# MRCS-Dual-3-Position-Semaphore-Controlle.net
KiCad netlist of a schematic drawn in EAGLE
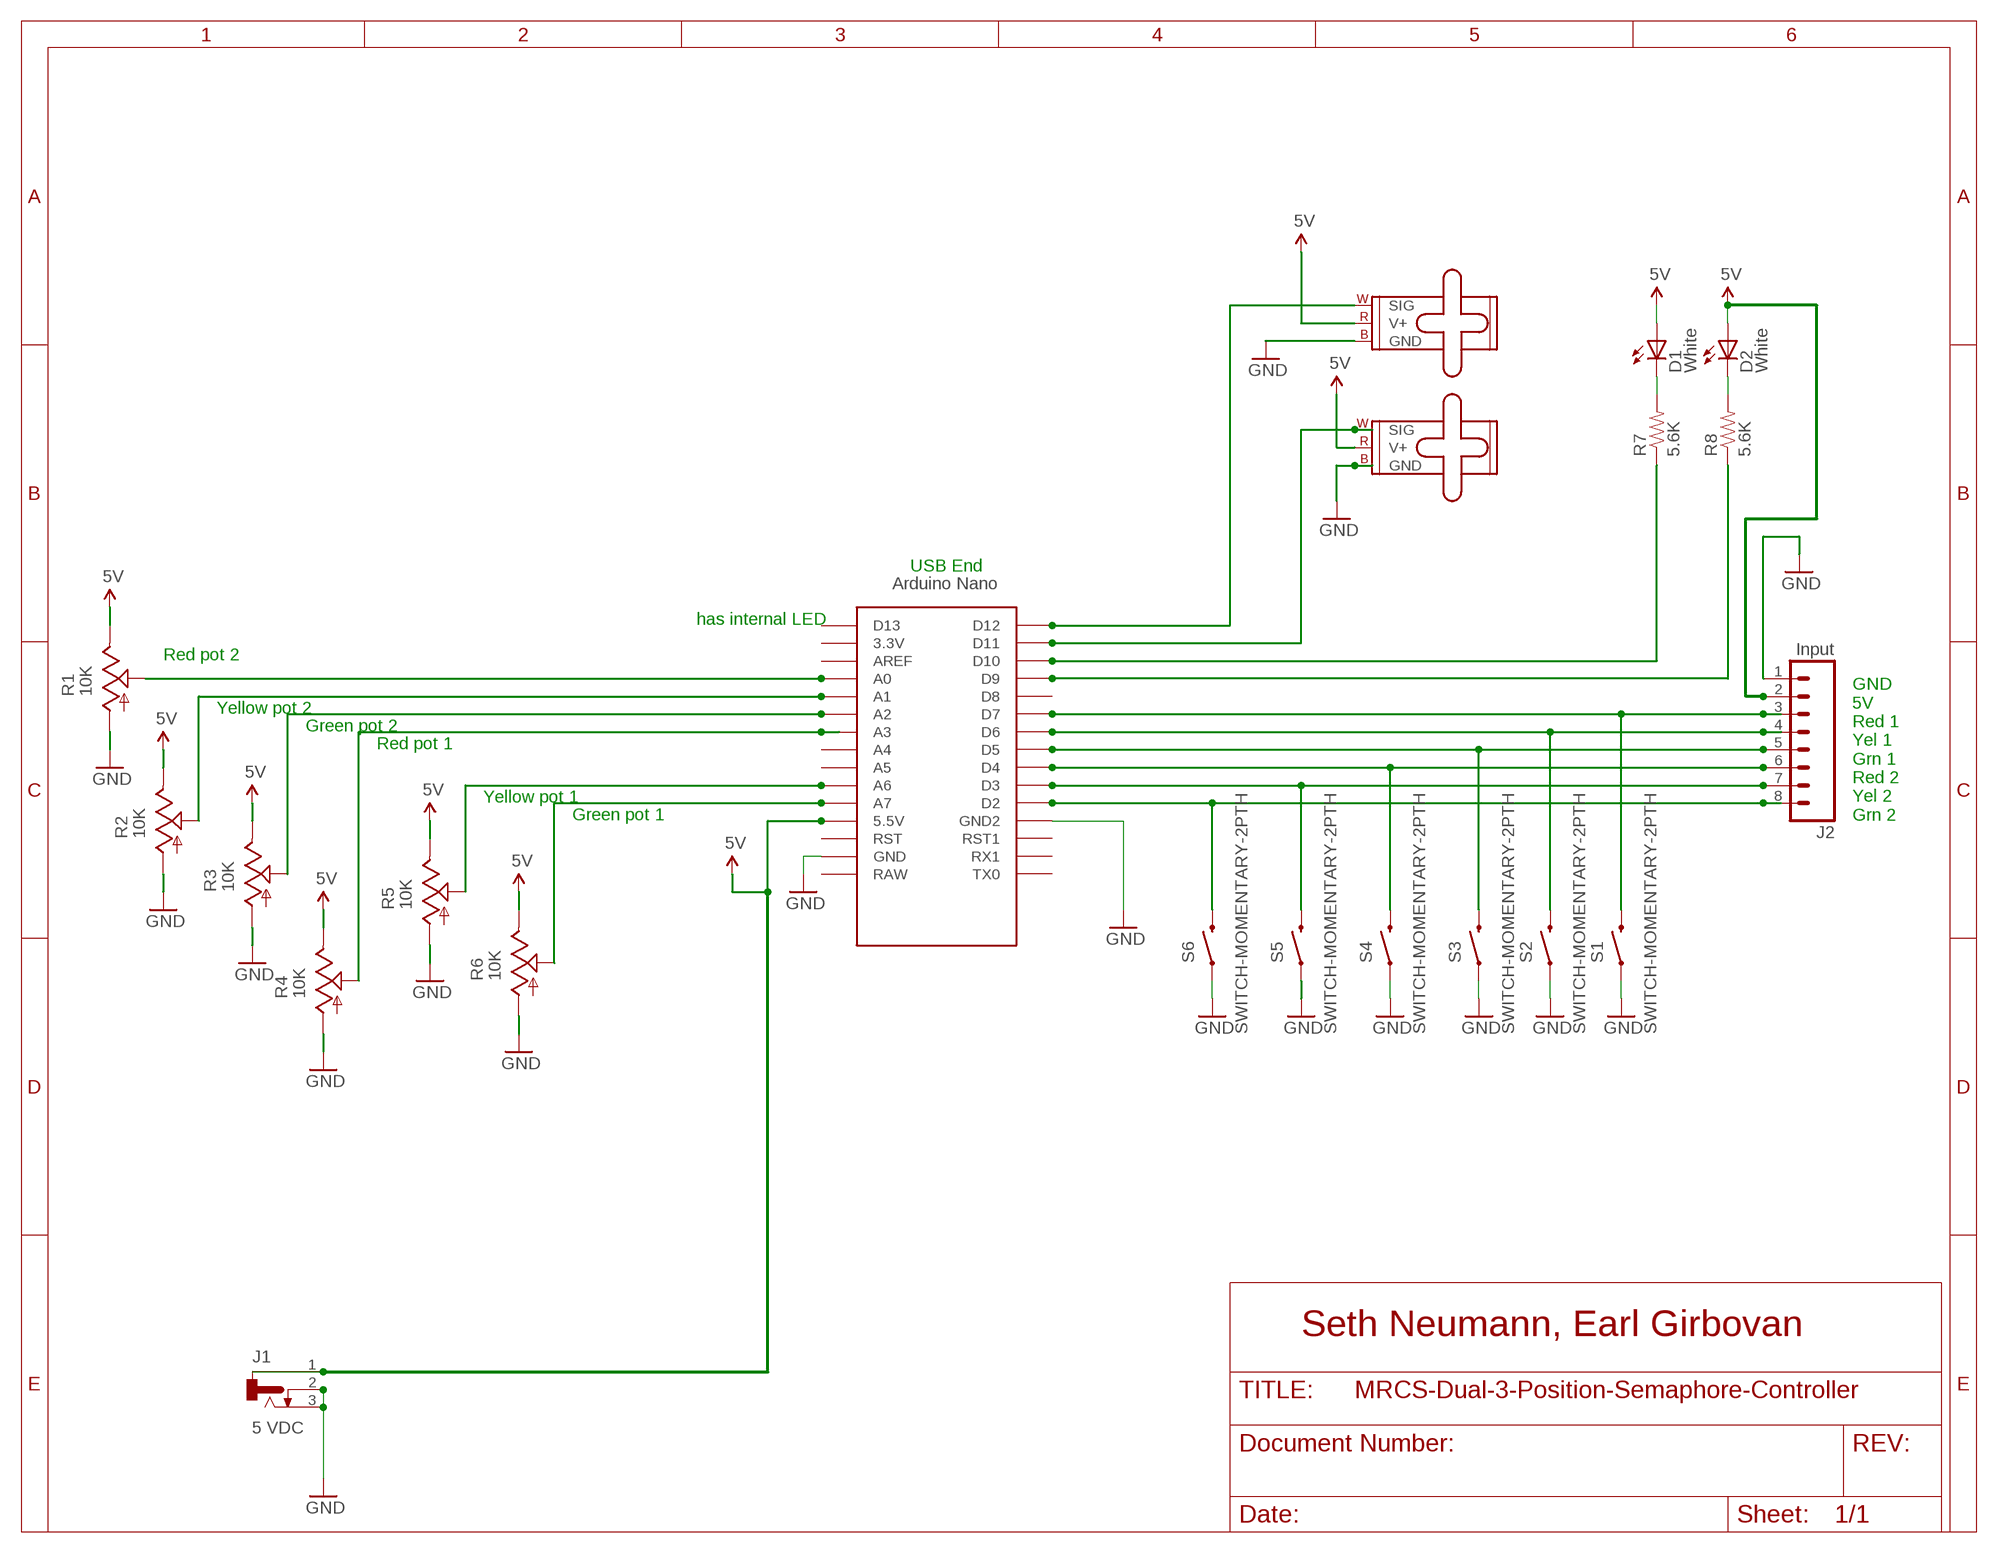
[diagram p0: schematic, sheet 1]

(export (version "E")
  (design (tool "Eeschema 10.0.6"))
  (components
    (comp (ref "D1")
      (value "White")
      (footprint "eagle-import:LED3MM")
      (libsource (lib "eagle-import") (part "LEDLED3MM"))
    )
    (comp (ref "D2")
      (value "White")
      (footprint "eagle-import:LED3MM")
      (libsource (lib "eagle-import") (part "LEDLED3MM"))
    )
    (comp (ref "J1")
      (value "5 VDC")
      (footprint "eagle-import:DCJ0202")
      (libsource (lib "eagle-import") (part "CONNECTOR-DC-POWER-RA"))
    )
    (comp (ref "J2")
      (value "Input")
      (footprint "eagle-import:1X08_LOCK")
      (libsource (lib "eagle-import") (part "CONNECTOR-M08LOCK"))
    )
    (comp (ref "M1")
      (value "SMALL_SERVO")
      (footprint "eagle-import:1X03")
      (libsource (lib "eagle-import") (part "SMALL_SERVO"))
    )
    (comp (ref "M2")
      (value "SMALL_SERVO")
      (footprint "eagle-import:1X03")
      (libsource (lib "eagle-import") (part "SMALL_SERVO"))
    )
    (comp (ref "NANO")
      (value "NANO")
      (footprint "eagle-import:NANO")
      (libsource (lib "eagle-import") (part "NANO"))
    )
    (comp (ref "R1")
      (value "10K")
      (footprint "eagle-import:RS3")
      (libsource (lib "eagle-import") (part "TRIM_US-RS3"))
    )
    (comp (ref "R2")
      (value "10K")
      (footprint "eagle-import:RS3")
      (libsource (lib "eagle-import") (part "TRIM_US-RS3"))
    )
    (comp (ref "R3")
      (value "10K")
      (footprint "eagle-import:RS3")
      (libsource (lib "eagle-import") (part "TRIM_US-RS3"))
    )
    (comp (ref "R4")
      (value "10K")
      (footprint "eagle-import:RS3")
      (libsource (lib "eagle-import") (part "TRIM_US-RS3"))
    )
    (comp (ref "R5")
      (value "10K")
      (footprint "eagle-import:RS3")
      (libsource (lib "eagle-import") (part "TRIM_US-RS3"))
    )
    (comp (ref "R6")
      (value "10K")
      (footprint "eagle-import:RS3")
      (libsource (lib "eagle-import") (part "TRIM_US-RS3"))
    )
    (comp (ref "R7")
      (value "5.6K")
      (footprint "eagle-import:AXIAL-0.4")
      (libsource (lib "eagle-import") (part "RESISTORPTH-1/4W"))
    )
    (comp (ref "R8")
      (value "5.6K")
      (footprint "eagle-import:AXIAL-0.4")
      (libsource (lib "eagle-import") (part "RESISTORPTH-1/4W"))
    )
    (comp (ref "S1")
      (value "SWITCH-MOMENTARY-2PTH")
      (footprint "eagle-import:TACTILE-PTH")
      (libsource (lib "eagle-import") (part "SWITCH-MOMENTARY-2PTH"))
    )
    (comp (ref "S2")
      (value "SWITCH-MOMENTARY-2PTH")
      (footprint "eagle-import:TACTILE-PTH")
      (libsource (lib "eagle-import") (part "SWITCH-MOMENTARY-2PTH"))
    )
    (comp (ref "S3")
      (value "SWITCH-MOMENTARY-2PTH")
      (footprint "eagle-import:TACTILE-PTH")
      (libsource (lib "eagle-import") (part "SWITCH-MOMENTARY-2PTH"))
    )
    (comp (ref "S4")
      (value "SWITCH-MOMENTARY-2PTH")
      (footprint "eagle-import:TACTILE-PTH")
      (libsource (lib "eagle-import") (part "SWITCH-MOMENTARY-2PTH"))
    )
    (comp (ref "S5")
      (value "SWITCH-MOMENTARY-2PTH")
      (footprint "eagle-import:TACTILE-PTH")
      (libsource (lib "eagle-import") (part "SWITCH-MOMENTARY-2PTH"))
    )
    (comp (ref "S6")
      (value "SWITCH-MOMENTARY-2PTH")
      (footprint "eagle-import:TACTILE-PTH")
      (libsource (lib "eagle-import") (part "SWITCH-MOMENTARY-2PTH"))
    )
  )
  (nets
    (net (code "1") (name "5V") (class "Default")
      (node (ref "D1") (pin "A") (pinfunction "A_A") (pintype "passive"))
      (node (ref "D2") (pin "A") (pinfunction "A_A") (pintype "passive"))
      (node (ref "J1") (pin "1") (pinfunction "1_1") (pintype "passive"))
      (node (ref "J2") (pin "2") (pinfunction "2_2") (pintype "passive"))
      (node (ref "M1") (pin "2") (pinfunction "V+_2") (pintype "bidirectional"))
      (node (ref "M2") (pin "2") (pinfunction "V+_2") (pintype "bidirectional"))
      (node (ref "NANO") (pin "5V") (pinfunction "5.5V_5V") (pintype "bidirectional"))
      (node (ref "R1") (pin "E") (pinfunction "E_E") (pintype "passive"))
      (node (ref "R2") (pin "E") (pinfunction "E_E") (pintype "passive"))
      (node (ref "R3") (pin "E") (pinfunction "E_E") (pintype "passive"))
      (node (ref "R4") (pin "E") (pinfunction "E_E") (pintype "passive"))
      (node (ref "R5") (pin "E") (pinfunction "E_E") (pintype "passive"))
      (node (ref "R6") (pin "E") (pinfunction "E_E") (pintype "passive"))
    )
    (net (code "2") (name "GND") (class "Default")
      (node (ref "J1") (pin "2") (pinfunction "2_2") (pintype "passive"))
      (node (ref "J1") (pin "3") (pinfunction "3_3") (pintype "passive"))
      (node (ref "J2") (pin "1") (pinfunction "1_1") (pintype "passive"))
      (node (ref "M1") (pin "3") (pinfunction "GND_3") (pintype "bidirectional"))
      (node (ref "M2") (pin "3") (pinfunction "GND_3") (pintype "bidirectional"))
      (node (ref "NANO") (pin "GND") (pinfunction "GND_GND") (pintype "bidirectional"))
      (node (ref "NANO") (pin "GND1") (pinfunction "GND2_GND1") (pintype "bidirectional"))
      (node (ref "R1") (pin "A") (pinfunction "A_A") (pintype "passive"))
      (node (ref "R2") (pin "A") (pinfunction "A_A") (pintype "passive"))
      (node (ref "R3") (pin "A") (pinfunction "A_A") (pintype "passive"))
      (node (ref "R4") (pin "A") (pinfunction "A_A") (pintype "passive"))
      (node (ref "R5") (pin "A") (pinfunction "A_A") (pintype "passive"))
      (node (ref "R6") (pin "A") (pinfunction "A_A") (pintype "passive"))
      (node (ref "S1") (pin "1") (pinfunction "1_1") (pintype "passive"))
      (node (ref "S2") (pin "1") (pinfunction "1_1") (pintype "passive"))
      (node (ref "S3") (pin "1") (pinfunction "1_1") (pintype "passive"))
      (node (ref "S4") (pin "1") (pinfunction "1_1") (pintype "passive"))
      (node (ref "S5") (pin "1") (pinfunction "1_1") (pintype "passive"))
      (node (ref "S6") (pin "1") (pinfunction "1_1") (pintype "passive"))
    )
    (net (code "3") (name "Net-(D1-C)") (class "Default")
      (node (ref "D1") (pin "K") (pinfunction "C_K") (pintype "passive"))
      (node (ref "R7") (pin "P$2") (pinfunction "2_P$2") (pintype "passive"))
    )
    (net (code "4") (name "Net-(D2-C)") (class "Default")
      (node (ref "D2") (pin "K") (pinfunction "C_K") (pintype "passive"))
      (node (ref "R8") (pin "P$2") (pinfunction "2_P$2") (pintype "passive"))
    )
    (net (code "5") (name "Net-(M1-SIG)") (class "Default")
      (node (ref "M1") (pin "1") (pinfunction "SIG_1") (pintype "bidirectional"))
      (node (ref "NANO") (pin "D12") (pinfunction "D12_D12") (pintype "bidirectional"))
    )
    (net (code "6") (name "Net-(M2-SIG)") (class "Default")
      (node (ref "M2") (pin "1") (pinfunction "SIG_1") (pintype "bidirectional"))
      (node (ref "NANO") (pin "D11") (pinfunction "D11_D11") (pintype "bidirectional"))
    )
    (net (code "7") (name "Net-(NANO-PadA0)") (class "Default")
      (node (ref "NANO") (pin "A0") (pinfunction "A0_A0") (pintype "bidirectional"))
      (node (ref "R1") (pin "S") (pinfunction "S_S") (pintype "passive"))
    )
    (net (code "8") (name "Net-(NANO-PadA1)") (class "Default")
      (node (ref "NANO") (pin "A1") (pinfunction "A1_A1") (pintype "bidirectional"))
      (node (ref "R2") (pin "S") (pinfunction "S_S") (pintype "passive"))
    )
    (net (code "9") (name "Net-(NANO-PadA2)") (class "Default")
      (node (ref "NANO") (pin "A2") (pinfunction "A2_A2") (pintype "bidirectional"))
      (node (ref "R3") (pin "S") (pinfunction "S_S") (pintype "passive"))
    )
    (net (code "10") (name "Net-(NANO-PadA3)") (class "Default")
      (node (ref "NANO") (pin "A3") (pinfunction "A3_A3") (pintype "bidirectional"))
      (node (ref "R4") (pin "S") (pinfunction "S_S") (pintype "passive"))
    )
    (net (code "11") (name "Net-(NANO-PadA6)") (class "Default")
      (node (ref "NANO") (pin "A6") (pinfunction "A6_A6") (pintype "bidirectional"))
      (node (ref "R5") (pin "S") (pinfunction "S_S") (pintype "passive"))
    )
    (net (code "12") (name "Net-(NANO-PadA7)") (class "Default")
      (node (ref "NANO") (pin "A7") (pinfunction "A7_A7") (pintype "bidirectional"))
      (node (ref "R6") (pin "S") (pinfunction "S_S") (pintype "passive"))
    )
    (net (code "13") (name "Net-(R7-1)") (class "Default")
      (node (ref "NANO") (pin "D10") (pinfunction "D10_D10") (pintype "bidirectional"))
      (node (ref "R7") (pin "P$1") (pinfunction "1_P$1") (pintype "passive"))
    )
    (net (code "14") (name "Net-(R8-1)") (class "Default")
      (node (ref "NANO") (pin "D9") (pinfunction "D9_D9") (pintype "bidirectional"))
      (node (ref "R8") (pin "P$1") (pinfunction "1_P$1") (pintype "passive"))
    )
    (net (code "15") (name "Net-(S1-2)") (class "Default")
      (node (ref "J2") (pin "3") (pinfunction "3_3") (pintype "passive"))
      (node (ref "NANO") (pin "D7") (pinfunction "D7_D7") (pintype "bidirectional"))
      (node (ref "S1") (pin "3") (pinfunction "2_3") (pintype "passive"))
    )
    (net (code "16") (name "Net-(S2-2)") (class "Default")
      (node (ref "J2") (pin "4") (pinfunction "4_4") (pintype "passive"))
      (node (ref "NANO") (pin "D6") (pinfunction "D6_D6") (pintype "bidirectional"))
      (node (ref "S2") (pin "3") (pinfunction "2_3") (pintype "passive"))
    )
    (net (code "17") (name "Net-(S3-2)") (class "Default")
      (node (ref "J2") (pin "5") (pinfunction "5_5") (pintype "passive"))
      (node (ref "NANO") (pin "D5") (pinfunction "D5_D5") (pintype "bidirectional"))
      (node (ref "S3") (pin "3") (pinfunction "2_3") (pintype "passive"))
    )
    (net (code "18") (name "Net-(S4-2)") (class "Default")
      (node (ref "J2") (pin "6") (pinfunction "6_6") (pintype "passive"))
      (node (ref "NANO") (pin "D4") (pinfunction "D4_D4") (pintype "bidirectional"))
      (node (ref "S4") (pin "3") (pinfunction "2_3") (pintype "passive"))
    )
    (net (code "19") (name "Net-(S5-2)") (class "Default")
      (node (ref "J2") (pin "7") (pinfunction "7_7") (pintype "passive"))
      (node (ref "NANO") (pin "D3") (pinfunction "D3_D3") (pintype "bidirectional"))
      (node (ref "S5") (pin "3") (pinfunction "2_3") (pintype "passive"))
    )
    (net (code "20") (name "Net-(S6-2)") (class "Default")
      (node (ref "J2") (pin "8") (pinfunction "8_8") (pintype "passive"))
      (node (ref "NANO") (pin "D2") (pinfunction "D2_D2") (pintype "bidirectional"))
      (node (ref "S6") (pin "3") (pinfunction "2_3") (pintype "passive"))
    )
    (net (code "21") (name "unconnected-(NANO-Pad3.3V)") (class "Default")
      (node (ref "NANO") (pin "3.3V") (pinfunction "3.3V_3.3V") (pintype "bidirectional"))
    )
    (net (code "22") (name "unconnected-(NANO-PadA4)") (class "Default")
      (node (ref "NANO") (pin "A4") (pinfunction "A4_A4") (pintype "bidirectional"))
    )
    (net (code "23") (name "unconnected-(NANO-PadA5)") (class "Default")
      (node (ref "NANO") (pin "A5") (pinfunction "A5_A5") (pintype "bidirectional"))
    )
    (net (code "24") (name "unconnected-(NANO-PadAREF)") (class "Default")
      (node (ref "NANO") (pin "AREF") (pinfunction "AREF_AREF") (pintype "bidirectional"))
    )
    (net (code "25") (name "unconnected-(NANO-PadD8)") (class "Default")
      (node (ref "NANO") (pin "D8") (pinfunction "D8_D8") (pintype "bidirectional"))
    )
    (net (code "26") (name "unconnected-(NANO-PadD13)") (class "Default")
      (node (ref "NANO") (pin "D13") (pinfunction "D13_D13") (pintype "bidirectional"))
    )
    (net (code "27") (name "unconnected-(NANO-PadRAW)") (class "Default")
      (node (ref "NANO") (pin "RAW") (pinfunction "RAW_RAW") (pintype "bidirectional"))
    )
    (net (code "28") (name "unconnected-(NANO-PadRST)") (class "Default")
      (node (ref "NANO") (pin "RST") (pinfunction "RST_RST") (pintype "bidirectional"))
    )
    (net (code "29") (name "unconnected-(NANO-PadRST1)") (class "Default")
      (node (ref "NANO") (pin "RST1") (pinfunction "RST1_RST1") (pintype "bidirectional"))
    )
    (net (code "30") (name "unconnected-(NANO-PadRX1)") (class "Default")
      (node (ref "NANO") (pin "RX1") (pinfunction "RX1_RX1") (pintype "bidirectional"))
    )
    (net (code "31") (name "unconnected-(NANO-PadTX0)") (class "Default")
      (node (ref "NANO") (pin "TX0") (pinfunction "TX0_TX0") (pintype "bidirectional"))
    )
  )
)
